# AVR_ISP_TestCircuit.net
KiCad netlist of a schematic drawn in EAGLE
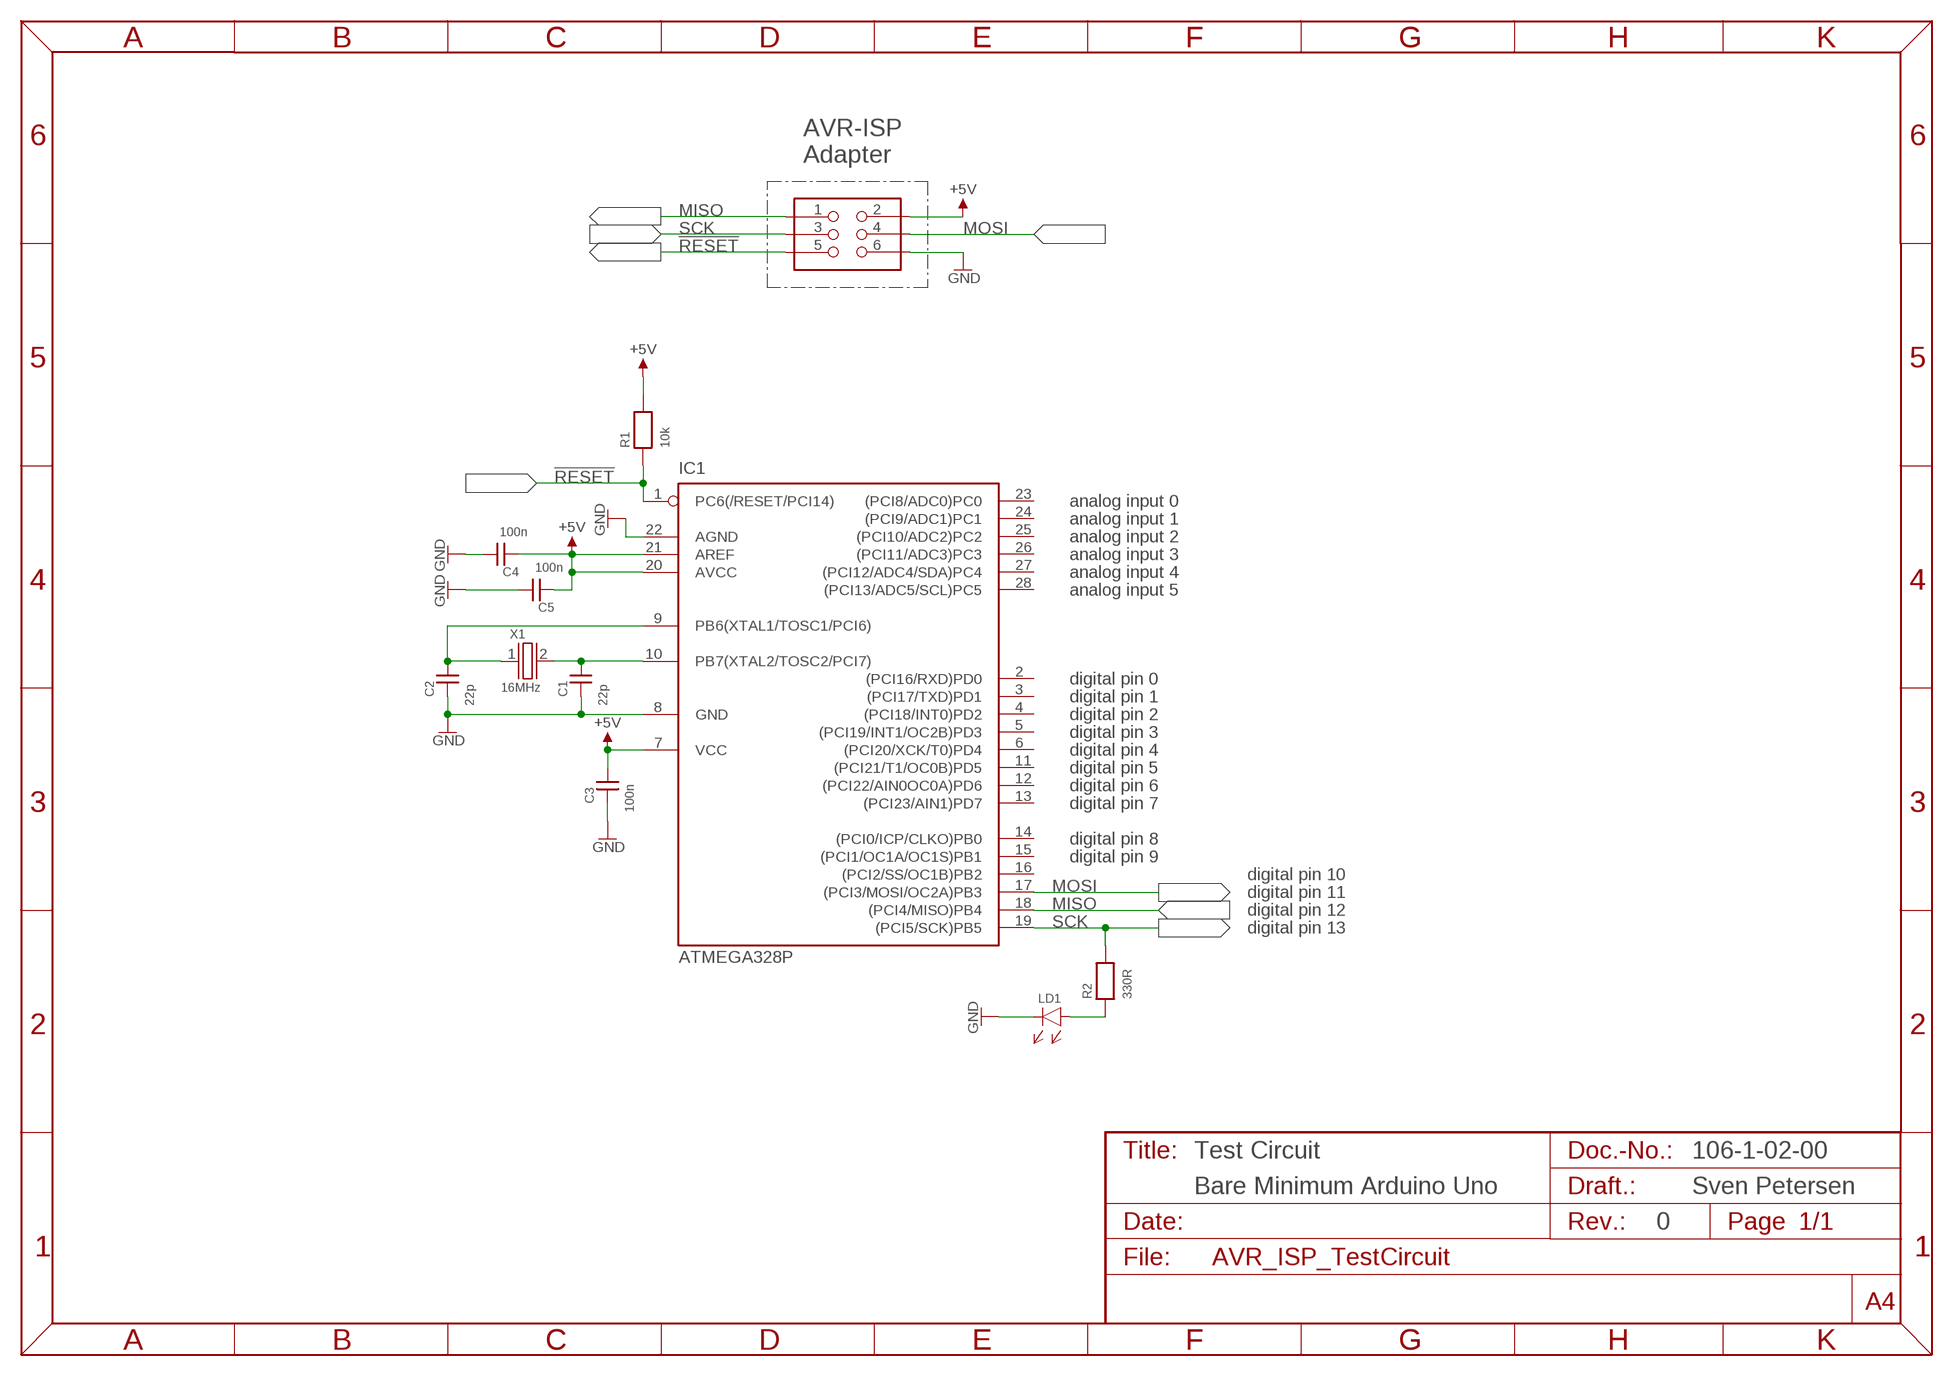
[diagram p0: schematic, sheet 1]

(export (version "E")
  (design (tool "Eeschema 10.0.6"))
  (components
    (comp (ref "C1")
      (value "22p")
      (footprint "eagle-import:C-5")
      (libsource (lib "eagle-import") (part "CAP02"))
    )
    (comp (ref "C2")
      (value "22p")
      (footprint "eagle-import:C-5")
      (libsource (lib "eagle-import") (part "CAP02"))
    )
    (comp (ref "C3")
      (value "100n")
      (footprint "eagle-import:C-5")
      (libsource (lib "eagle-import") (part "CAP02"))
    )
    (comp (ref "C4")
      (value "100n")
      (footprint "eagle-import:C-5")
      (libsource (lib "eagle-import") (part "CAP02"))
    )
    (comp (ref "C5")
      (value "100n")
      (footprint "eagle-import:C-5")
      (libsource (lib "eagle-import") (part "CAP02"))
    )
    (comp (ref "IC1")
      (value "ATMEGA328P")
      (footprint "eagle-import:DIL28-3-ROUND")
      (libsource (lib "eagle-import") (part "ATMEGA328PROUND"))
    )
    (comp (ref "J1")
      (value "WSL 6G")
      (footprint "eagle-import:2X03WV")
      (libsource (lib "eagle-import") (part "2X03WV"))
    )
    (comp (ref "LD1")
      (value "5MM")
      (footprint "eagle-import:5MM")
      (libsource (lib "eagle-import") (part "5MM"))
    )
    (comp (ref "R1")
      (value "10k")
      (footprint "eagle-import:R-10")
      (libsource (lib "eagle-import") (part "RES04"))
    )
    (comp (ref "R2")
      (value "330R")
      (footprint "eagle-import:R-10")
      (libsource (lib "eagle-import") (part "RES04"))
    )
    (comp (ref "X1")
      (value "16MHz")
      (footprint "eagle-import:HC49SLF")
      (libsource (lib "eagle-import") (part "HC49SLF"))
    )
  )
  (nets
    (net (code "1") (name "+5V") (class "Default")
      (node (ref "C3") (pin "2") (pinfunction "2_2") (pintype "passive"))
      (node (ref "C4") (pin "1") (pinfunction "1_1") (pintype "passive"))
      (node (ref "C5") (pin "1") (pinfunction "1_1") (pintype "passive"))
      (node (ref "IC1") (pin "20") (pinfunction "AVCC_20") (pintype "bidirectional"))
      (node (ref "IC1") (pin "21") (pinfunction "AREF_21") (pintype "bidirectional"))
      (node (ref "IC1") (pin "7") (pinfunction "VCC_7") (pintype "bidirectional"))
      (node (ref "J1") (pin "2") (pinfunction "2_2") (pintype "passive"))
      (node (ref "R1") (pin "2") (pinfunction "2_2") (pintype "passive"))
    )
    (net (code "2") (name "/MISO") (class "Default")
      (node (ref "IC1") (pin "18") (pinfunction "(PCI4/MISO)PB4_18") (pintype "bidirectional"))
      (node (ref "J1") (pin "1") (pinfunction "1_1") (pintype "passive"))
    )
    (net (code "3") (name "/MOSI") (class "Default")
      (node (ref "IC1") (pin "17") (pinfunction "(PCI3/MOSI/OC2A)PB3_17") (pintype "bidirectional"))
      (node (ref "J1") (pin "4") (pinfunction "4_4") (pintype "passive"))
    )
    (net (code "4") (name "/SCK") (class "Default")
      (node (ref "IC1") (pin "19") (pinfunction "(PCI5/SCK)PB5_19") (pintype "bidirectional"))
      (node (ref "J1") (pin "3") (pinfunction "3_3") (pintype "passive"))
      (node (ref "R2") (pin "2") (pinfunction "2_2") (pintype "passive"))
    )
    (net (code "5") (name "/~{RESET}") (class "Default")
      (node (ref "IC1") (pin "1") (pinfunction "PC6(/RESET/PCI14)_1") (pintype "bidirectional"))
      (node (ref "J1") (pin "5") (pinfunction "5_5") (pintype "passive"))
      (node (ref "R1") (pin "1") (pinfunction "1_1") (pintype "passive"))
    )
    (net (code "6") (name "GND") (class "Default")
      (node (ref "C1") (pin "1") (pinfunction "1_1") (pintype "passive"))
      (node (ref "C2") (pin "1") (pinfunction "1_1") (pintype "passive"))
      (node (ref "C3") (pin "1") (pinfunction "1_1") (pintype "passive"))
      (node (ref "C4") (pin "2") (pinfunction "2_2") (pintype "passive"))
      (node (ref "C5") (pin "2") (pinfunction "2_2") (pintype "passive"))
      (node (ref "IC1") (pin "22") (pinfunction "AGND_22") (pintype "bidirectional"))
      (node (ref "IC1") (pin "8") (pinfunction "GND_8") (pintype "bidirectional"))
      (node (ref "J1") (pin "6") (pinfunction "6_6") (pintype "passive"))
      (node (ref "LD1") (pin "C") (pinfunction "K_C") (pintype "bidirectional"))
    )
    (net (code "7") (name "Net-(IC1-PB6(XTAL1{slash}TOSC1{slash}PCI6))") (class "Default")
      (node (ref "C2") (pin "2") (pinfunction "2_2") (pintype "passive"))
      (node (ref "IC1") (pin "9") (pinfunction "PB6(XTAL1/TOSC1/PCI6)_9") (pintype "bidirectional"))
      (node (ref "X1") (pin "1") (pinfunction "1_1") (pintype "passive"))
    )
    (net (code "8") (name "Net-(IC1-PB7(XTAL2{slash}TOSC2{slash}PCI7))") (class "Default")
      (node (ref "C1") (pin "2") (pinfunction "2_2") (pintype "passive"))
      (node (ref "IC1") (pin "10") (pinfunction "PB7(XTAL2/TOSC2/PCI7)_10") (pintype "bidirectional"))
      (node (ref "X1") (pin "2") (pinfunction "2_2") (pintype "passive"))
    )
    (net (code "9") (name "Net-(LD1-PadA)") (class "Default")
      (node (ref "LD1") (pin "A") (pinfunction "A_A") (pintype "bidirectional"))
      (node (ref "R2") (pin "1") (pinfunction "1_1") (pintype "passive"))
    )
    (net (code "10") (name "unconnected-(IC1-(PCI0{slash}ICP{slash}CLKO)PB0-Pad14)") (class "Default")
      (node (ref "IC1") (pin "14") (pinfunction "(PCI0/ICP/CLKO)PB0_14") (pintype "bidirectional"))
    )
    (net (code "11") (name "unconnected-(IC1-(PCI1{slash}OC1A{slash}OC1S)PB1-Pad15)") (class "Default")
      (node (ref "IC1") (pin "15") (pinfunction "(PCI1/OC1A/OC1S)PB1_15") (pintype "bidirectional"))
    )
    (net (code "12") (name "unconnected-(IC1-(PCI2{slash}SS{slash}OC1B)PB2-Pad16)") (class "Default")
      (node (ref "IC1") (pin "16") (pinfunction "(PCI2/SS/OC1B)PB2_16") (pintype "bidirectional"))
    )
    (net (code "13") (name "unconnected-(IC1-(PCI8{slash}ADC0)PC0-Pad23)") (class "Default")
      (node (ref "IC1") (pin "23") (pinfunction "(PCI8/ADC0)PC0_23") (pintype "bidirectional"))
    )
    (net (code "14") (name "unconnected-(IC1-(PCI9{slash}ADC1)PC1-Pad24)") (class "Default")
      (node (ref "IC1") (pin "24") (pinfunction "(PCI9/ADC1)PC1_24") (pintype "bidirectional"))
    )
    (net (code "15") (name "unconnected-(IC1-(PCI10{slash}ADC2)PC2-Pad25)") (class "Default")
      (node (ref "IC1") (pin "25") (pinfunction "(PCI10/ADC2)PC2_25") (pintype "bidirectional"))
    )
    (net (code "16") (name "unconnected-(IC1-(PCI11{slash}ADC3)PC3-Pad26)") (class "Default")
      (node (ref "IC1") (pin "26") (pinfunction "(PCI11/ADC3)PC3_26") (pintype "bidirectional"))
    )
    (net (code "17") (name "unconnected-(IC1-(PCI12{slash}ADC4{slash}SDA)PC4-Pad27)") (class "Default")
      (node (ref "IC1") (pin "27") (pinfunction "(PCI12/ADC4/SDA)PC4_27") (pintype "bidirectional"))
    )
    (net (code "18") (name "unconnected-(IC1-(PCI13{slash}ADC5{slash}SCL)PC5-Pad28)") (class "Default")
      (node (ref "IC1") (pin "28") (pinfunction "(PCI13/ADC5/SCL)PC5_28") (pintype "bidirectional"))
    )
    (net (code "19") (name "unconnected-(IC1-(PCI16{slash}RXD)PD0-Pad2)") (class "Default")
      (node (ref "IC1") (pin "2") (pinfunction "(PCI16/RXD)PD0_2") (pintype "bidirectional"))
    )
    (net (code "20") (name "unconnected-(IC1-(PCI17{slash}TXD)PD1-Pad3)") (class "Default")
      (node (ref "IC1") (pin "3") (pinfunction "(PCI17/TXD)PD1_3") (pintype "bidirectional"))
    )
    (net (code "21") (name "unconnected-(IC1-(PCI18{slash}INT0)PD2-Pad4)") (class "Default")
      (node (ref "IC1") (pin "4") (pinfunction "(PCI18/INT0)PD2_4") (pintype "bidirectional"))
    )
    (net (code "22") (name "unconnected-(IC1-(PCI19{slash}INT1{slash}OC2B)PD3-Pad5)") (class "Default")
      (node (ref "IC1") (pin "5") (pinfunction "(PCI19/INT1/OC2B)PD3_5") (pintype "bidirectional"))
    )
    (net (code "23") (name "unconnected-(IC1-(PCI20{slash}XCK{slash}T0)PD4-Pad6)") (class "Default")
      (node (ref "IC1") (pin "6") (pinfunction "(PCI20/XCK/T0)PD4_6") (pintype "bidirectional"))
    )
    (net (code "24") (name "unconnected-(IC1-(PCI21{slash}T1{slash}OC0B)PD5-Pad11)") (class "Default")
      (node (ref "IC1") (pin "11") (pinfunction "(PCI21/T1/OC0B)PD5_11") (pintype "bidirectional"))
    )
    (net (code "25") (name "unconnected-(IC1-(PCI22{slash}AIN0OC0A)PD6-Pad12)") (class "Default")
      (node (ref "IC1") (pin "12") (pinfunction "(PCI22/AIN0OC0A)PD6_12") (pintype "bidirectional"))
    )
    (net (code "26") (name "unconnected-(IC1-(PCI23{slash}AIN1)PD7-Pad13)") (class "Default")
      (node (ref "IC1") (pin "13") (pinfunction "(PCI23/AIN1)PD7_13") (pintype "bidirectional"))
    )
  )
)
